# precharge_circuit.net
KiCad netlist of a schematic drawn in Altium Designer
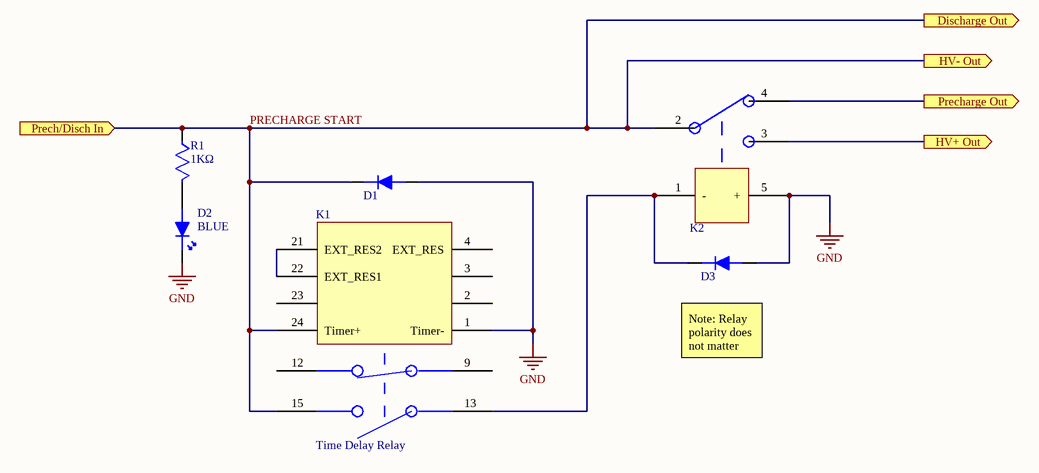
[diagram p0: precharge_circuit.SchDoc]

(export (version "E")
  (design (tool "Eeschema 10.0.6"))
  (components
    (comp (ref "D1")
      (value "SD560BTR")
      (footprint "DIODE")
      (description "DIODE GEN PURP 600V 5A SMB")
      (fields (field (name "MANUFACTURER") "SMC"))
      (libsource (lib "sdc_prech_schlib") (part "SD560BTR"))
    )
    (comp (ref "D2")
      (value "BLUE")
      (footprint "LED 0603")
      (description "LED BLUE CLEAR CHIP SMD")
      (fields
        (field (name "MANUFACTURER") "Vishay Lite-On")
        (field (name "MANUFACTURER PART NUMBER") "LTST-C191TBKT-5A")
      )
      (libsource (lib "sdc_prech_schlib") (part "LTST-C191TBKT-5A"))
    )
    (comp (ref "D3")
      (value "SD560BTR")
      (footprint "DIODE")
      (description "DIODE GEN PURP 600V 5A SMB")
      (fields (field (name "MANUFACTURER") "SMC"))
      (libsource (lib "sdc_prech_schlib") (part "SD560BTR"))
    )
    (comp (ref "K1")
      (value "Time Delay Relay")
      (footprint "RELAY TIMED")
      (description "Time Delay & Timing Relays 12VDC 1s-10m Contact SPST-NO+SPST-NC")
      (fields (field (name "MANUFACTURER") "Omron") (field (name "MANUFACTURER PART NUMBER") "H3FA-A-DC12"))
      (libsource (lib "sdc_prech_schlib") (part "H3FA-A-DC12"))
    )
    (comp (ref "K2")
      (value "G5Q-14-DC12")
      (footprint "RELAY SPDT PRECHARGE")
      (description "Electromechanical Relay SPDT 5(NO)/3(NC)ADC/10(NO)/3(NC)AAC 12VDC 360Ohm Through Hole")
      (fields (field (name "MANUFACTURER") "Omron"))
      (libsource (lib "sdc_prech_schlib") (part "G5Q-14-DC12"))
    )
    (comp (ref "R1")
      (value "1KΩ")
      (footprint "RESISTOR CRCW0603")
      (description "RES SMD 1K OHM 1% 1/10W 0603")
      (fields
        (field (name "MANUFACTURER") "Vishay Dale")
        (field (name "MANUFACTURER PART NUMBER") "CRCW06031K00FKEA")
      )
      (libsource (lib "sdc_prech_schlib") (part "CRCW06031K00FKEA"))
    )
  )
  (nets
    (net (code "1") (name "/HV+ Out") (class "Default") (node (ref "K2") (pin "3") (pintype "passive")))
    (net (code "2") (name "/PRECHARGE START") (class "Default")
      (node (ref "D1") (pin "2") (pinfunction "2_2") (pintype "passive"))
      (node (ref "K1") (pin "15") (pinfunction "NO-1_15") (pintype "passive"))
      (node (ref "K1") (pin "24") (pinfunction "Timer+_24") (pintype "passive"))
      (node (ref "K2") (pin "2") (pintype "passive"))
      (node (ref "R1") (pin "1") (pinfunction "1_1") (pintype "passive"))
    )
    (net (code "3") (name "/Precharge Out") (class "Default") (node (ref "K2") (pin "4") (pintype "passive")))
    (net (code "4") (name "GND") (class "Default")
      (node (ref "D1") (pin "1") (pinfunction "1_1") (pintype "passive"))
      (node (ref "D2") (pin "2") (pinfunction "2_2") (pintype "passive"))
      (node (ref "D3") (pin "1") (pinfunction "1_1") (pintype "passive"))
      (node (ref "K1") (pin "1") (pinfunction "Timer-_1") (pintype "passive"))
      (node (ref "K2") (pin "5") (pinfunction "+_5") (pintype "passive"))
    )
    (net (code "5") (name "Net-(D2-Pad1)") (class "Default")
      (node (ref "D2") (pin "1") (pinfunction "1_1") (pintype "passive"))
      (node (ref "R1") (pin "2") (pinfunction "2_2") (pintype "passive"))
    )
    (net (code "6") (name "Net-(K1-EXT_RES1)") (class "Default")
      (node (ref "K1") (pin "21") (pinfunction "EXT_RES2_21") (pintype "passive"))
      (node (ref "K1") (pin "22") (pinfunction "EXT_RES1_22") (pintype "passive"))
    )
    (net (code "7") (name "Net-(K1-NO-2)") (class "Default")
      (node (ref "D3") (pin "2") (pinfunction "2_2") (pintype "passive"))
      (node (ref "K1") (pin "13") (pinfunction "NO-2_13") (pintype "passive"))
      (node (ref "K2") (pin "1") (pinfunction "-_1") (pintype "passive"))
    )
    (net (code "8") (name "unconnected-(K1-EXT_RES-Pad4)") (class "Default")
      (node (ref "K1") (pin "4") (pinfunction "EXT_RES_4") (pintype "passive"))
    )
    (net (code "9") (name "unconnected-(K1-NC-1-Pad9)") (class "Default")
      (node (ref "K1") (pin "9") (pinfunction "NC-1_9") (pintype "passive"))
    )
    (net (code "10") (name "unconnected-(K1-NC-2-Pad12)") (class "Default")
      (node (ref "K1") (pin "12") (pinfunction "NC-2_12") (pintype "passive"))
    )
    (net (code "11") (name "unconnected-(K1-Pad2)") (class "Default")
      (node (ref "K1") (pin "2") (pinfunction "2_2") (pintype "passive"))
    )
    (net (code "12") (name "unconnected-(K1-Pad3)") (class "Default")
      (node (ref "K1") (pin "3") (pinfunction "3_3") (pintype "passive"))
    )
    (net (code "13") (name "unconnected-(K1-Pad23)") (class "Default")
      (node (ref "K1") (pin "23") (pinfunction "23_23") (pintype "passive"))
    )
  )
)
